# Supply_5V.net
KiCad netlist of a schematic drawn in Altium Designer
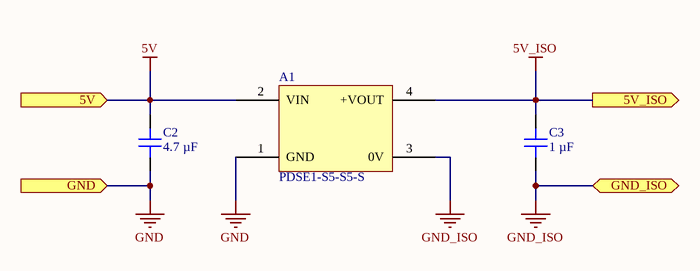
[diagram p0: Supply 5V.SchDoc]

(export (version "E")
  (design (tool "Eeschema 10.0.6"))
  (components
    (comp (ref "A1")
      (value "PDSE1-S5-S5-S")
      (footprint "CUI PDSE1-S")
      (description "DC DC CONVERTER 5V 1W")
      (fields (field (name "MANUFACTURER") "CUI Inc."))
      (libsource (lib "altiumlibrary.com") (part "CUI PDSE1-S"))
    )
    (comp (ref "C2")
      (value "4.7 µF")
      (footprint "CAP 0805_2012")
      (description "CAP CER 4.7UF 25V X7R 0805")
      (fields
        (field (name "PART NUMBER") "CL21B475KAFNNNE")
        (field (name "MANUFACTURER") "Samsung Electro-Mechanics")
      )
      (libsource (lib "altiumlibrary.com") (part "Capacitor"))
    )
    (comp (ref "C3")
      (value "1 µF")
      (footprint "CAP 0805_2012")
      (description "CAP CER 1UF 50V X7R 0805")
      (fields
        (field (name "PART NUMBER") "GCJ21BR71H105KA01L")
        (field (name "MANUFACTURER") "Murata Electronics")
      )
      (libsource (lib "altiumlibrary.com") (part "Capacitor"))
    )
  )
  (nets
    (net (code "1") (name "5V") (class "Default")
      (node (ref "A1") (pin "2") (pinfunction "VIN_2") (pintype "passive"))
      (node (ref "C2") (pin "2") (pinfunction "2_2") (pintype "passive"))
    )
    (net (code "2") (name "5V_ISO") (class "Default")
      (node (ref "A1") (pin "4") (pinfunction "+VOUT_4") (pintype "passive"))
      (node (ref "C3") (pin "2") (pinfunction "2_2") (pintype "passive"))
    )
    (net (code "3") (name "GND") (class "Default")
      (node (ref "A1") (pin "1") (pinfunction "GND_1") (pintype "passive"))
      (node (ref "C2") (pin "1") (pinfunction "1_1") (pintype "passive"))
    )
    (net (code "4") (name "GND_ISO") (class "Default")
      (node (ref "A1") (pin "3") (pinfunction "0V_3") (pintype "passive"))
      (node (ref "C3") (pin "1") (pinfunction "1_1") (pintype "passive"))
    )
  )
)
